# Backplane.net
KiCad netlist of a schematic drawn in EAGLE
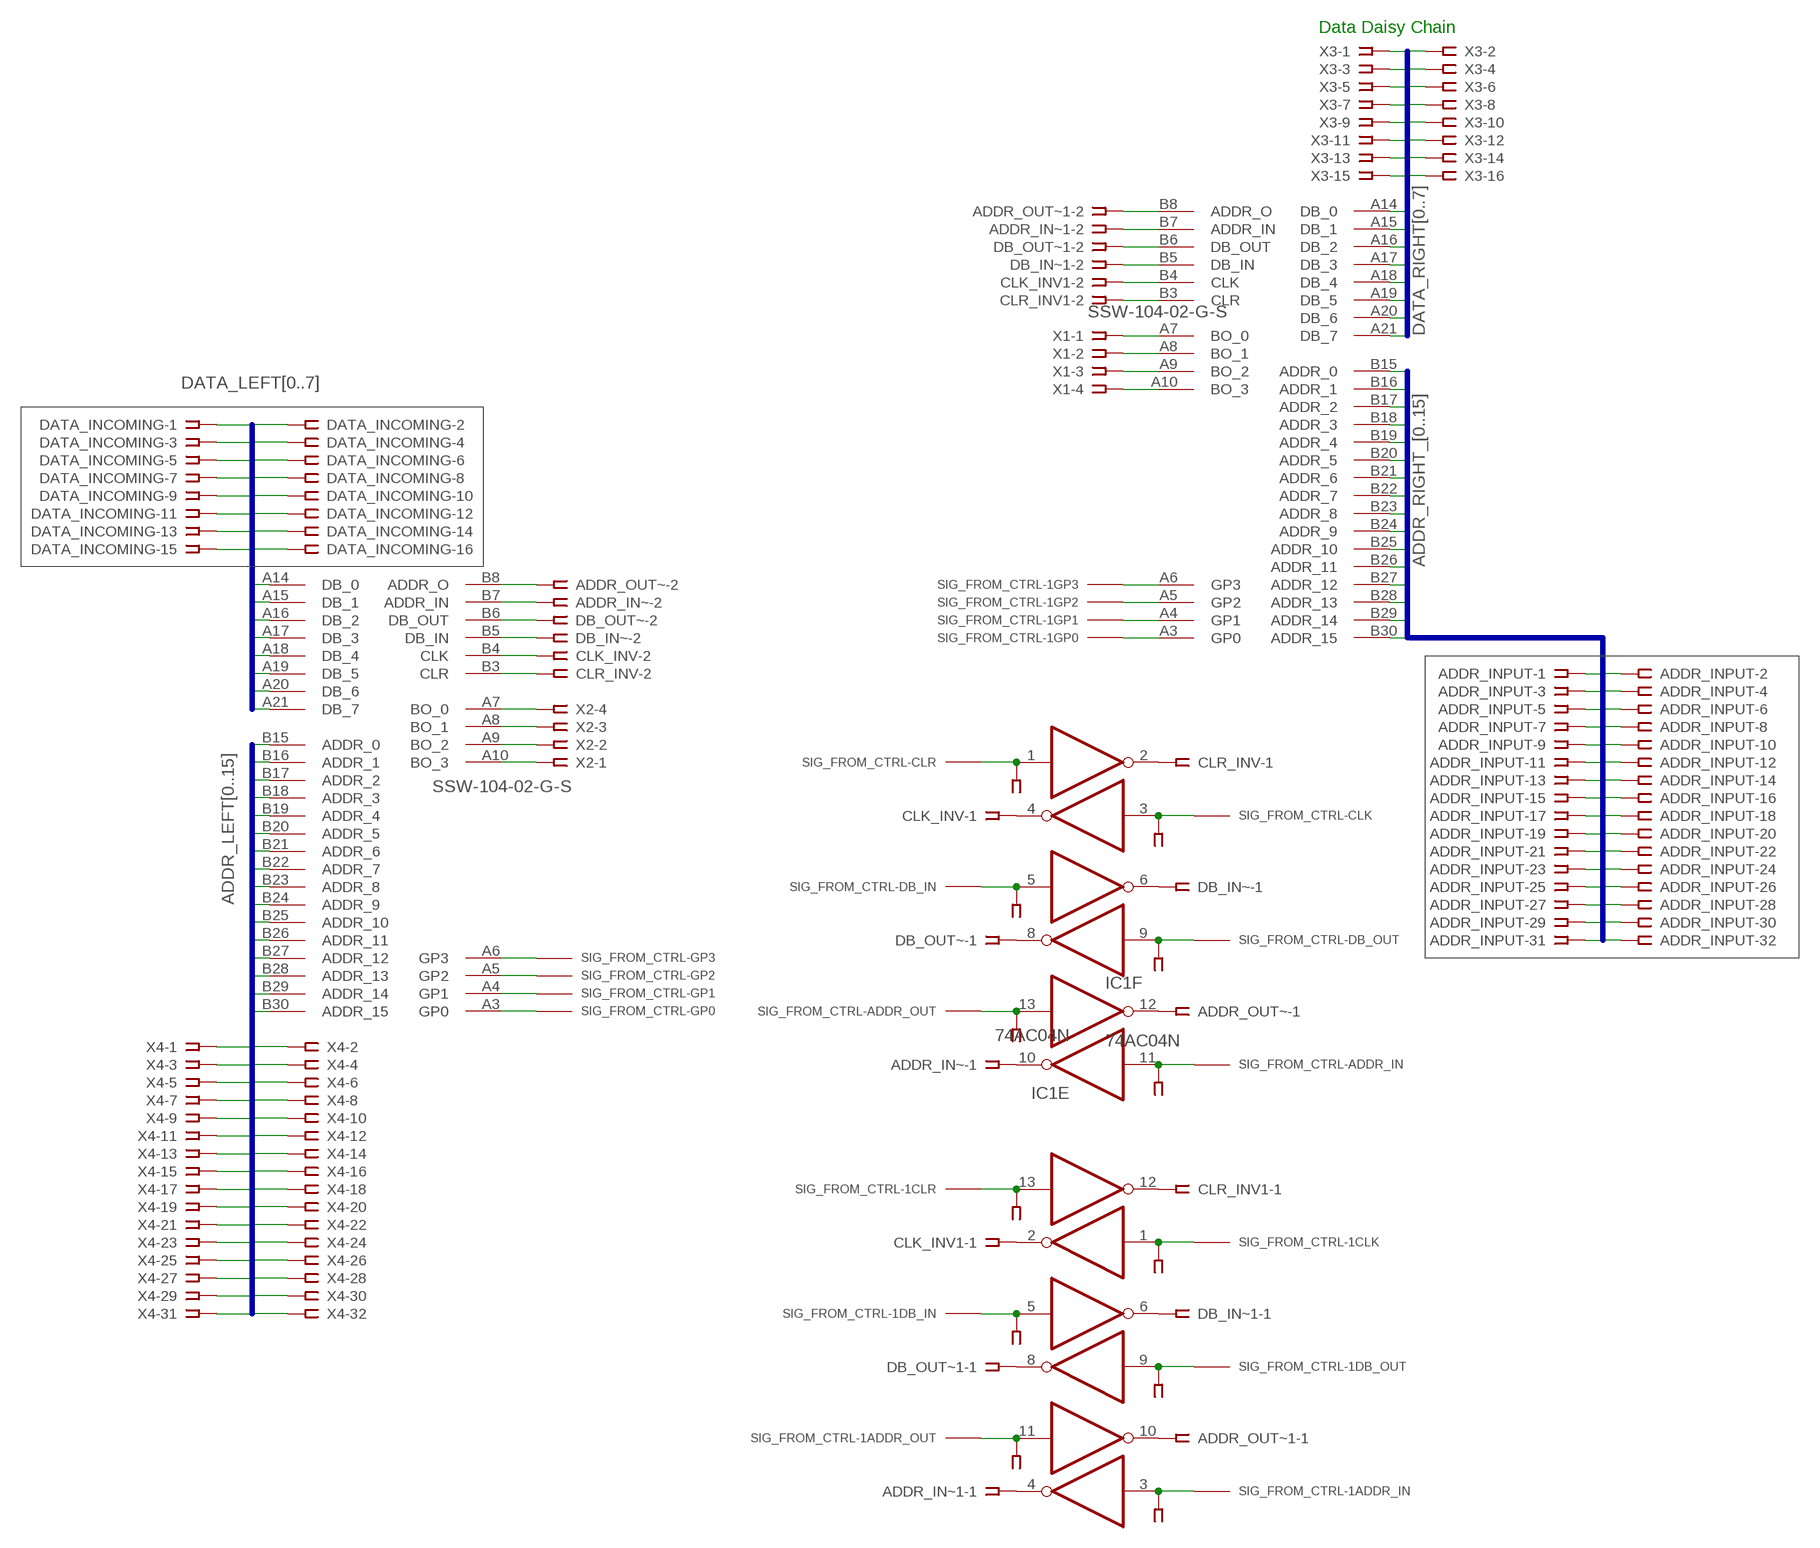
[diagram p0: schematic, sheet 1]

(export (version "E")
  (design (tool "Eeschema 10.0.6"))
  (components
    (comp (ref "ADDR_INPUT")
      (value "SSW-116-02-G-D")
      (footprint "eagle-import:SSW-116-02-G-D")
      (fields (field (name "MF") "Samtec Inc."))
      (libsource (lib "eagle-import") (part "SSW-116-02-G-D"))
    )
    (comp (ref "ADDR_IN~")
      (value "SSW-103-02-G-S")
      (footprint "eagle-import:SSW-103-02-G-S")
      (fields (field (name "MF") "Samtec Inc."))
      (libsource (lib "eagle-import") (part "SSW-103-02-G-S"))
    )
    (comp (ref "ADDR_IN~1")
      (value "SSW-103-02-G-S")
      (footprint "eagle-import:SSW-103-02-G-S")
      (fields (field (name "MF") "Samtec Inc."))
      (libsource (lib "eagle-import") (part "SSW-103-02-G-S"))
    )
    (comp (ref "ADDR_OUT~")
      (value "SSW-103-02-G-S")
      (footprint "eagle-import:SSW-103-02-G-S")
      (fields (field (name "MF") "Samtec Inc."))
      (libsource (lib "eagle-import") (part "SSW-103-02-G-S"))
    )
    (comp (ref "ADDR_OUT~1")
      (value "SSW-103-02-G-S")
      (footprint "eagle-import:SSW-103-02-G-S")
      (fields (field (name "MF") "Samtec Inc."))
      (libsource (lib "eagle-import") (part "SSW-103-02-G-S"))
    )
    (comp (ref "CLK_INV")
      (value "SSW-103-02-G-S")
      (footprint "eagle-import:SSW-103-02-G-S")
      (fields (field (name "MF") "Samtec Inc."))
      (libsource (lib "eagle-import") (part "SSW-103-02-G-S"))
    )
    (comp (ref "CLK_INV1")
      (value "SSW-103-02-G-S")
      (footprint "eagle-import:SSW-103-02-G-S")
      (fields (field (name "MF") "Samtec Inc."))
      (libsource (lib "eagle-import") (part "SSW-103-02-G-S"))
    )
    (comp (ref "CLR_INV")
      (value "SSW-103-02-G-S")
      (footprint "eagle-import:SSW-103-02-G-S")
      (fields (field (name "MF") "Samtec Inc."))
      (libsource (lib "eagle-import") (part "SSW-103-02-G-S"))
    )
    (comp (ref "CLR_INV1")
      (value "SSW-103-02-G-S")
      (footprint "eagle-import:SSW-103-02-G-S")
      (fields (field (name "MF") "Samtec Inc."))
      (libsource (lib "eagle-import") (part "SSW-103-02-G-S"))
    )
    (comp (ref "DATA_INCOMING")
      (value "SSW-108-02-G-D")
      (footprint "eagle-import:SSW-108-02-G-D")
      (fields (field (name "MF") "Samtec Inc."))
      (libsource (lib "eagle-import") (part "SSW-108-02-G-D"))
    )
    (comp (ref "DB_IN~")
      (value "SSW-103-02-G-S")
      (footprint "eagle-import:SSW-103-02-G-S")
      (fields (field (name "MF") "Samtec Inc."))
      (libsource (lib "eagle-import") (part "SSW-103-02-G-S"))
    )
    (comp (ref "DB_IN~1")
      (value "SSW-103-02-G-S")
      (footprint "eagle-import:SSW-103-02-G-S")
      (fields (field (name "MF") "Samtec Inc."))
      (libsource (lib "eagle-import") (part "SSW-103-02-G-S"))
    )
    (comp (ref "DB_OUT~")
      (value "SSW-103-02-G-S")
      (footprint "eagle-import:SSW-103-02-G-S")
      (fields (field (name "MF") "Samtec Inc."))
      (libsource (lib "eagle-import") (part "SSW-103-02-G-S"))
    )
    (comp (ref "DB_OUT~1")
      (value "SSW-103-02-G-S")
      (footprint "eagle-import:SSW-103-02-G-S")
      (fields (field (name "MF") "Samtec Inc."))
      (libsource (lib "eagle-import") (part "SSW-103-02-G-S"))
    )
    (comp (ref "IC1")
      (value "74AC04N")
      (footprint "eagle-import:DIL14")
      (libsource (lib "eagle-import") (part "7404NAC"))
    )
    (comp (ref "IC2")
      (value "74AC04N")
      (footprint "eagle-import:DIL14")
      (libsource (lib "eagle-import") (part "7404NAC"))
    )
    (comp (ref "SIG_FROM_CTRL-")
      (value "CONTROL_SIG-INT")
      (footprint "eagle-import:CONTROL_SIG-INT-FOOT")
      (libsource (lib "eagle-import") (part "CONTROL_SIG-INT"))
    )
    (comp (ref "SIG_FROM_CTRL-1")
      (value "CONTROL_SIG-INT")
      (footprint "eagle-import:CONTROL_SIG-INT-FOOT")
      (libsource (lib "eagle-import") (part "CONTROL_SIG-INT"))
    )
    (comp (ref "U$1")
      (value "BACKPLATE_INTERFACEHEADER")
      (footprint "eagle-import:PCI_INTERFACE")
      (libsource (lib "eagle-import") (part "BACKPLATE_INTERFACEHEADER"))
    )
    (comp (ref "U$2")
      (value "BACKPLATE_INTERFACEHEADER")
      (footprint "eagle-import:PCI_INTERFACE")
      (libsource (lib "eagle-import") (part "BACKPLATE_INTERFACEHEADER"))
    )
    (comp (ref "X1")
      (value "SSW-104-02-G-S")
      (footprint "eagle-import:SSW-104-02-G-S")
      (fields (field (name "MF") "Samtec Inc."))
      (libsource (lib "eagle-import") (part "SSW-104-02-G-S"))
    )
    (comp (ref "X2")
      (value "SSW-104-02-G-S")
      (footprint "eagle-import:SSW-104-02-G-S")
      (fields (field (name "MF") "Samtec Inc."))
      (libsource (lib "eagle-import") (part "SSW-104-02-G-S"))
    )
    (comp (ref "X3")
      (value "SSW-108-02-G-D")
      (footprint "eagle-import:SSW-108-02-G-D")
      (fields (field (name "MF") "Samtec Inc."))
      (libsource (lib "eagle-import") (part "SSW-108-02-G-D"))
    )
    (comp (ref "X4")
      (value "SSW-116-02-G-D")
      (footprint "eagle-import:SSW-116-02-G-D")
      (fields (field (name "MF") "Samtec Inc."))
      (libsource (lib "eagle-import") (part "SSW-116-02-G-D"))
    )
  )
  (nets
    (net (code "1") (name "/ADDR_LEFT0") (class "Default")
      (node (ref "U$2") (pin "B15") (pinfunction "ADDR_0_B15") (pintype "bidirectional"))
      (node (ref "X4") (pin "1") (pinfunction "1_1") (pintype "passive"))
      (node (ref "X4") (pin "2") (pinfunction "1_2") (pintype "passive"))
    )
    (net (code "2") (name "/ADDR_LEFT1") (class "Default")
      (node (ref "U$2") (pin "B16") (pinfunction "ADDR_1_B16") (pintype "bidirectional"))
      (node (ref "X4") (pin "3") (pinfunction "1_3") (pintype "passive"))
      (node (ref "X4") (pin "4") (pinfunction "1_4") (pintype "passive"))
    )
    (net (code "3") (name "/ADDR_LEFT2") (class "Default")
      (node (ref "U$2") (pin "B17") (pinfunction "ADDR_2_B17") (pintype "bidirectional"))
      (node (ref "X4") (pin "5") (pinfunction "1_5") (pintype "passive"))
      (node (ref "X4") (pin "6") (pinfunction "1_6") (pintype "passive"))
    )
    (net (code "4") (name "/ADDR_LEFT3") (class "Default")
      (node (ref "U$2") (pin "B18") (pinfunction "ADDR_3_B18") (pintype "bidirectional"))
      (node (ref "X4") (pin "7") (pinfunction "1_7") (pintype "passive"))
      (node (ref "X4") (pin "8") (pinfunction "1_8") (pintype "passive"))
    )
    (net (code "5") (name "/ADDR_LEFT4") (class "Default")
      (node (ref "U$2") (pin "B19") (pinfunction "ADDR_4_B19") (pintype "bidirectional"))
      (node (ref "X4") (pin "10") (pinfunction "1_10") (pintype "passive"))
      (node (ref "X4") (pin "9") (pinfunction "1_9") (pintype "passive"))
    )
    (net (code "6") (name "/ADDR_LEFT5") (class "Default")
      (node (ref "U$2") (pin "B20") (pinfunction "ADDR_5_B20") (pintype "bidirectional"))
      (node (ref "X4") (pin "11") (pinfunction "1_11") (pintype "passive"))
      (node (ref "X4") (pin "12") (pinfunction "1_12") (pintype "passive"))
    )
    (net (code "7") (name "/ADDR_LEFT6") (class "Default")
      (node (ref "U$2") (pin "B21") (pinfunction "ADDR_6_B21") (pintype "bidirectional"))
      (node (ref "X4") (pin "13") (pinfunction "1_13") (pintype "passive"))
      (node (ref "X4") (pin "14") (pinfunction "1_14") (pintype "passive"))
    )
    (net (code "8") (name "/ADDR_LEFT7") (class "Default")
      (node (ref "U$2") (pin "B22") (pinfunction "ADDR_7_B22") (pintype "bidirectional"))
      (node (ref "X4") (pin "15") (pinfunction "1_15") (pintype "passive"))
      (node (ref "X4") (pin "16") (pinfunction "1_16") (pintype "passive"))
    )
    (net (code "9") (name "/ADDR_LEFT8") (class "Default")
      (node (ref "U$2") (pin "B23") (pinfunction "ADDR_8_B23") (pintype "bidirectional"))
      (node (ref "X4") (pin "17") (pinfunction "1_17") (pintype "passive"))
      (node (ref "X4") (pin "18") (pinfunction "1_18") (pintype "passive"))
    )
    (net (code "10") (name "/ADDR_LEFT9") (class "Default")
      (node (ref "U$2") (pin "B24") (pinfunction "ADDR_9_B24") (pintype "bidirectional"))
      (node (ref "X4") (pin "19") (pinfunction "1_19") (pintype "passive"))
      (node (ref "X4") (pin "20") (pinfunction "1_20") (pintype "passive"))
    )
    (net (code "11") (name "/ADDR_LEFT10") (class "Default")
      (node (ref "U$2") (pin "B25") (pinfunction "ADDR_10_B25") (pintype "bidirectional"))
      (node (ref "X4") (pin "21") (pinfunction "1_21") (pintype "passive"))
      (node (ref "X4") (pin "22") (pinfunction "1_22") (pintype "passive"))
    )
    (net (code "12") (name "/ADDR_LEFT11") (class "Default")
      (node (ref "U$2") (pin "B26") (pinfunction "ADDR_11_B26") (pintype "bidirectional"))
      (node (ref "X4") (pin "23") (pinfunction "1_23") (pintype "passive"))
      (node (ref "X4") (pin "24") (pinfunction "1_24") (pintype "passive"))
    )
    (net (code "13") (name "/ADDR_LEFT12") (class "Default")
      (node (ref "U$2") (pin "B27") (pinfunction "ADDR_12_B27") (pintype "bidirectional"))
      (node (ref "X4") (pin "25") (pinfunction "1_25") (pintype "passive"))
      (node (ref "X4") (pin "26") (pinfunction "1_26") (pintype "passive"))
    )
    (net (code "14") (name "/ADDR_LEFT13") (class "Default")
      (node (ref "U$2") (pin "B28") (pinfunction "ADDR_13_B28") (pintype "bidirectional"))
      (node (ref "X4") (pin "27") (pinfunction "1_27") (pintype "passive"))
      (node (ref "X4") (pin "28") (pinfunction "1_28") (pintype "passive"))
    )
    (net (code "15") (name "/ADDR_LEFT14") (class "Default")
      (node (ref "U$2") (pin "B29") (pinfunction "ADDR_14_B29") (pintype "bidirectional"))
      (node (ref "X4") (pin "29") (pinfunction "1_29") (pintype "passive"))
      (node (ref "X4") (pin "30") (pinfunction "1_30") (pintype "passive"))
    )
    (net (code "16") (name "/ADDR_LEFT15") (class "Default")
      (node (ref "U$2") (pin "B30") (pinfunction "ADDR_15_B30") (pintype "bidirectional"))
      (node (ref "X4") (pin "31") (pinfunction "1_31") (pintype "passive"))
      (node (ref "X4") (pin "32") (pinfunction "1_32") (pintype "passive"))
    )
    (net (code "18") (name "/ADDR_RIGHT_0") (class "Default")
      (node (ref "ADDR_INPUT") (pin "1") (pinfunction "1_1") (pintype "passive"))
      (node (ref "ADDR_INPUT") (pin "2") (pinfunction "1_2") (pintype "passive"))
      (node (ref "U$1") (pin "B15") (pinfunction "ADDR_0_B15") (pintype "bidirectional"))
    )
    (net (code "19") (name "/ADDR_RIGHT_1") (class "Default")
      (node (ref "ADDR_INPUT") (pin "3") (pinfunction "1_3") (pintype "passive"))
      (node (ref "ADDR_INPUT") (pin "4") (pinfunction "1_4") (pintype "passive"))
      (node (ref "U$1") (pin "B16") (pinfunction "ADDR_1_B16") (pintype "bidirectional"))
    )
    (net (code "20") (name "/ADDR_RIGHT_2") (class "Default")
      (node (ref "ADDR_INPUT") (pin "5") (pinfunction "1_5") (pintype "passive"))
      (node (ref "ADDR_INPUT") (pin "6") (pinfunction "1_6") (pintype "passive"))
      (node (ref "U$1") (pin "B17") (pinfunction "ADDR_2_B17") (pintype "bidirectional"))
    )
    (net (code "21") (name "/ADDR_RIGHT_3") (class "Default")
      (node (ref "ADDR_INPUT") (pin "7") (pinfunction "1_7") (pintype "passive"))
      (node (ref "ADDR_INPUT") (pin "8") (pinfunction "1_8") (pintype "passive"))
      (node (ref "U$1") (pin "B18") (pinfunction "ADDR_3_B18") (pintype "bidirectional"))
    )
    (net (code "22") (name "/ADDR_RIGHT_4") (class "Default")
      (node (ref "ADDR_INPUT") (pin "10") (pinfunction "1_10") (pintype "passive"))
      (node (ref "ADDR_INPUT") (pin "9") (pinfunction "1_9") (pintype "passive"))
      (node (ref "U$1") (pin "B19") (pinfunction "ADDR_4_B19") (pintype "bidirectional"))
    )
    (net (code "23") (name "/ADDR_RIGHT_5") (class "Default")
      (node (ref "ADDR_INPUT") (pin "11") (pinfunction "1_11") (pintype "passive"))
      (node (ref "ADDR_INPUT") (pin "12") (pinfunction "1_12") (pintype "passive"))
      (node (ref "U$1") (pin "B20") (pinfunction "ADDR_5_B20") (pintype "bidirectional"))
    )
    (net (code "24") (name "/ADDR_RIGHT_6") (class "Default")
      (node (ref "ADDR_INPUT") (pin "13") (pinfunction "1_13") (pintype "passive"))
      (node (ref "ADDR_INPUT") (pin "14") (pinfunction "1_14") (pintype "passive"))
      (node (ref "U$1") (pin "B21") (pinfunction "ADDR_6_B21") (pintype "bidirectional"))
    )
    (net (code "25") (name "/ADDR_RIGHT_7") (class "Default")
      (node (ref "ADDR_INPUT") (pin "15") (pinfunction "1_15") (pintype "passive"))
      (node (ref "ADDR_INPUT") (pin "16") (pinfunction "1_16") (pintype "passive"))
      (node (ref "U$1") (pin "B22") (pinfunction "ADDR_7_B22") (pintype "bidirectional"))
    )
    (net (code "26") (name "/ADDR_RIGHT_8") (class "Default")
      (node (ref "ADDR_INPUT") (pin "17") (pinfunction "1_17") (pintype "passive"))
      (node (ref "ADDR_INPUT") (pin "18") (pinfunction "1_18") (pintype "passive"))
      (node (ref "U$1") (pin "B23") (pinfunction "ADDR_8_B23") (pintype "bidirectional"))
    )
    (net (code "27") (name "/ADDR_RIGHT_9") (class "Default")
      (node (ref "ADDR_INPUT") (pin "19") (pinfunction "1_19") (pintype "passive"))
      (node (ref "ADDR_INPUT") (pin "20") (pinfunction "1_20") (pintype "passive"))
      (node (ref "U$1") (pin "B24") (pinfunction "ADDR_9_B24") (pintype "bidirectional"))
    )
    (net (code "28") (name "/ADDR_RIGHT_10") (class "Default")
      (node (ref "ADDR_INPUT") (pin "21") (pinfunction "1_21") (pintype "passive"))
      (node (ref "ADDR_INPUT") (pin "22") (pinfunction "1_22") (pintype "passive"))
      (node (ref "U$1") (pin "B25") (pinfunction "ADDR_10_B25") (pintype "bidirectional"))
    )
    (net (code "29") (name "/ADDR_RIGHT_11") (class "Default")
      (node (ref "ADDR_INPUT") (pin "23") (pinfunction "1_23") (pintype "passive"))
      (node (ref "ADDR_INPUT") (pin "24") (pinfunction "1_24") (pintype "passive"))
      (node (ref "U$1") (pin "B26") (pinfunction "ADDR_11_B26") (pintype "bidirectional"))
    )
    (net (code "30") (name "/ADDR_RIGHT_12") (class "Default")
      (node (ref "ADDR_INPUT") (pin "25") (pinfunction "1_25") (pintype "passive"))
      (node (ref "ADDR_INPUT") (pin "26") (pinfunction "1_26") (pintype "passive"))
      (node (ref "U$1") (pin "B27") (pinfunction "ADDR_12_B27") (pintype "bidirectional"))
    )
    (net (code "31") (name "/ADDR_RIGHT_13") (class "Default")
      (node (ref "ADDR_INPUT") (pin "27") (pinfunction "1_27") (pintype "passive"))
      (node (ref "ADDR_INPUT") (pin "28") (pinfunction "1_28") (pintype "passive"))
      (node (ref "U$1") (pin "B28") (pinfunction "ADDR_13_B28") (pintype "bidirectional"))
    )
    (net (code "32") (name "/ADDR_RIGHT_14") (class "Default")
      (node (ref "ADDR_INPUT") (pin "29") (pinfunction "1_29") (pintype "passive"))
      (node (ref "ADDR_INPUT") (pin "30") (pinfunction "1_30") (pintype "passive"))
      (node (ref "U$1") (pin "B29") (pinfunction "ADDR_14_B29") (pintype "bidirectional"))
    )
    (net (code "33") (name "/ADDR_RIGHT_15") (class "Default")
      (node (ref "ADDR_INPUT") (pin "31") (pinfunction "1_31") (pintype "passive"))
      (node (ref "ADDR_INPUT") (pin "32") (pinfunction "1_32") (pintype "passive"))
      (node (ref "U$1") (pin "B30") (pinfunction "ADDR_15_B30") (pintype "bidirectional"))
    )
    (net (code "35") (name "/DATA_LEFT0") (class "Default")
      (node (ref "DATA_INCOMING") (pin "1") (pinfunction "1_1") (pintype "passive"))
      (node (ref "DATA_INCOMING") (pin "2") (pinfunction "1_2") (pintype "passive"))
      (node (ref "U$2") (pin "A14") (pinfunction "DB_0_A14") (pintype "bidirectional"))
    )
    (net (code "36") (name "/DATA_LEFT1") (class "Default")
      (node (ref "DATA_INCOMING") (pin "3") (pinfunction "1_3") (pintype "passive"))
      (node (ref "DATA_INCOMING") (pin "4") (pinfunction "1_4") (pintype "passive"))
      (node (ref "U$2") (pin "A15") (pinfunction "DB_1_A15") (pintype "bidirectional"))
    )
    (net (code "37") (name "/DATA_LEFT2") (class "Default")
      (node (ref "DATA_INCOMING") (pin "5") (pinfunction "1_5") (pintype "passive"))
      (node (ref "DATA_INCOMING") (pin "6") (pinfunction "1_6") (pintype "passive"))
      (node (ref "U$2") (pin "A16") (pinfunction "DB_2_A16") (pintype "bidirectional"))
    )
    (net (code "38") (name "/DATA_LEFT3") (class "Default")
      (node (ref "DATA_INCOMING") (pin "7") (pinfunction "1_7") (pintype "passive"))
      (node (ref "DATA_INCOMING") (pin "8") (pinfunction "1_8") (pintype "passive"))
      (node (ref "U$2") (pin "A17") (pinfunction "DB_3_A17") (pintype "bidirectional"))
    )
    (net (code "39") (name "/DATA_LEFT4") (class "Default")
      (node (ref "DATA_INCOMING") (pin "10") (pinfunction "1_10") (pintype "passive"))
      (node (ref "DATA_INCOMING") (pin "9") (pinfunction "1_9") (pintype "passive"))
      (node (ref "U$2") (pin "A18") (pinfunction "DB_4_A18") (pintype "bidirectional"))
    )
    (net (code "40") (name "/DATA_LEFT5") (class "Default")
      (node (ref "DATA_INCOMING") (pin "11") (pinfunction "1_11") (pintype "passive"))
      (node (ref "DATA_INCOMING") (pin "12") (pinfunction "1_12") (pintype "passive"))
      (node (ref "U$2") (pin "A19") (pinfunction "DB_5_A19") (pintype "bidirectional"))
    )
    (net (code "41") (name "/DATA_LEFT6") (class "Default")
      (node (ref "DATA_INCOMING") (pin "13") (pinfunction "1_13") (pintype "passive"))
      (node (ref "DATA_INCOMING") (pin "14") (pinfunction "1_14") (pintype "passive"))
      (node (ref "U$2") (pin "A20") (pinfunction "DB_6_A20") (pintype "bidirectional"))
    )
    (net (code "42") (name "/DATA_LEFT7") (class "Default")
      (node (ref "DATA_INCOMING") (pin "15") (pinfunction "1_15") (pintype "passive"))
      (node (ref "DATA_INCOMING") (pin "16") (pinfunction "1_16") (pintype "passive"))
      (node (ref "U$2") (pin "A21") (pinfunction "DB_7_A21") (pintype "bidirectional"))
    )
    (net (code "43") (name "/DATA_RIGHT0") (class "Default")
      (node (ref "U$1") (pin "A14") (pinfunction "DB_0_A14") (pintype "bidirectional"))
      (node (ref "X3") (pin "1") (pinfunction "1_1") (pintype "passive"))
      (node (ref "X3") (pin "2") (pinfunction "1_2") (pintype "passive"))
    )
    (net (code "44") (name "/DATA_RIGHT1") (class "Default")
      (node (ref "U$1") (pin "A15") (pinfunction "DB_1_A15") (pintype "bidirectional"))
      (node (ref "X3") (pin "3") (pinfunction "1_3") (pintype "passive"))
      (node (ref "X3") (pin "4") (pinfunction "1_4") (pintype "passive"))
    )
    (net (code "45") (name "/DATA_RIGHT2") (class "Default")
      (node (ref "U$1") (pin "A16") (pinfunction "DB_2_A16") (pintype "bidirectional"))
      (node (ref "X3") (pin "5") (pinfunction "1_5") (pintype "passive"))
      (node (ref "X3") (pin "6") (pinfunction "1_6") (pintype "passive"))
    )
    (net (code "46") (name "/DATA_RIGHT3") (class "Default")
      (node (ref "U$1") (pin "A17") (pinfunction "DB_3_A17") (pintype "bidirectional"))
      (node (ref "X3") (pin "7") (pinfunction "1_7") (pintype "passive"))
      (node (ref "X3") (pin "8") (pinfunction "1_8") (pintype "passive"))
    )
    (net (code "47") (name "/DATA_RIGHT4") (class "Default")
      (node (ref "U$1") (pin "A18") (pinfunction "DB_4_A18") (pintype "bidirectional"))
      (node (ref "X3") (pin "10") (pinfunction "1_10") (pintype "passive"))
      (node (ref "X3") (pin "9") (pinfunction "1_9") (pintype "passive"))
    )
    (net (code "48") (name "/DATA_RIGHT5") (class "Default")
      (node (ref "U$1") (pin "A19") (pinfunction "DB_5_A19") (pintype "bidirectional"))
      (node (ref "X3") (pin "11") (pinfunction "1_11") (pintype "passive"))
      (node (ref "X3") (pin "12") (pinfunction "1_12") (pintype "passive"))
    )
    (net (code "49") (name "/DATA_RIGHT6") (class "Default")
      (node (ref "U$1") (pin "A20") (pinfunction "DB_6_A20") (pintype "bidirectional"))
      (node (ref "X3") (pin "13") (pinfunction "1_13") (pintype "passive"))
      (node (ref "X3") (pin "14") (pinfunction "1_14") (pintype "passive"))
    )
    (net (code "50") (name "/DATA_RIGHT7") (class "Default")
      (node (ref "U$1") (pin "A21") (pinfunction "DB_7_A21") (pintype "bidirectional"))
      (node (ref "X3") (pin "15") (pinfunction "1_15") (pintype "passive"))
      (node (ref "X3") (pin "16") (pinfunction "1_16") (pintype "passive"))
    )
    (net (code "52") (name "Net-(ADDR_IN~1B-1)") (class "Default")
      (node (ref "ADDR_IN~1") (pin "2") (pinfunction "1_2") (pintype "passive"))
      (node (ref "U$1") (pin "B7") (pinfunction "ADDR_IN_B7") (pintype "bidirectional"))
    )
    (net (code "53") (name "Net-(ADDR_IN~1C-1)") (class "Default")
      (node (ref "ADDR_IN~1") (pin "3") (pinfunction "1_3") (pintype "passive"))
      (node (ref "IC2") (pin "3") (pinfunction "I_3") (pintype "input"))
      (node (ref "SIG_FROM_CTRL-1") (pin "ADDR_IN") (pinfunction "0_ADDR_IN") (pintype "bidirectional"))
    )
    (net (code "54") (name "Net-(ADDR_IN~B-1)") (class "Default")
      (node (ref "ADDR_IN~") (pin "2") (pinfunction "1_2") (pintype "passive"))
      (node (ref "U$2") (pin "B7") (pinfunction "ADDR_IN_B7") (pintype "bidirectional"))
    )
    (net (code "55") (name "Net-(ADDR_IN~C-1)") (class "Default")
      (node (ref "ADDR_IN~") (pin "3") (pinfunction "1_3") (pintype "passive"))
      (node (ref "IC1") (pin "11") (pinfunction "I_11") (pintype "input"))
      (node (ref "SIG_FROM_CTRL-") (pin "ADDR_IN") (pinfunction "0_ADDR_IN") (pintype "bidirectional"))
    )
    (net (code "56") (name "Net-(ADDR_OUT~1B-1)") (class "Default")
      (node (ref "ADDR_OUT~1") (pin "2") (pinfunction "1_2") (pintype "passive"))
      (node (ref "U$1") (pin "B8") (pinfunction "ADDR_O_B8") (pintype "bidirectional"))
    )
    (net (code "57") (name "Net-(ADDR_OUT~1C-1)") (class "Default")
      (node (ref "ADDR_OUT~1") (pin "3") (pinfunction "1_3") (pintype "passive"))
      (node (ref "IC2") (pin "11") (pinfunction "I_11") (pintype "input"))
      (node (ref "SIG_FROM_CTRL-1") (pin "ADDR_OT") (pinfunction "0_ADDR_OT") (pintype "bidirectional"))
    )
    (net (code "58") (name "Net-(ADDR_OUT~B-1)") (class "Default")
      (node (ref "ADDR_OUT~") (pin "2") (pinfunction "1_2") (pintype "passive"))
      (node (ref "U$2") (pin "B8") (pinfunction "ADDR_O_B8") (pintype "bidirectional"))
    )
    (net (code "59") (name "Net-(ADDR_OUT~C-1)") (class "Default")
      (node (ref "ADDR_OUT~") (pin "3") (pinfunction "1_3") (pintype "passive"))
      (node (ref "IC1") (pin "13") (pinfunction "I_13") (pintype "input"))
      (node (ref "SIG_FROM_CTRL-") (pin "ADDR_OT") (pinfunction "0_ADDR_OT") (pintype "bidirectional"))
    )
    (net (code "60") (name "Net-(CLK_INV1B-1)") (class "Default")
      (node (ref "CLK_INV1") (pin "2") (pinfunction "1_2") (pintype "passive"))
      (node (ref "U$1") (pin "B4") (pinfunction "CLK_B4") (pintype "bidirectional"))
    )
    (net (code "61") (name "Net-(CLK_INV1C-1)") (class "Default")
      (node (ref "CLK_INV1") (pin "3") (pinfunction "1_3") (pintype "passive"))
      (node (ref "IC2") (pin "1") (pinfunction "I_1") (pintype "input"))
      (node (ref "SIG_FROM_CTRL-1") (pin "CLK") (pinfunction "0_CLK") (pintype "bidirectional"))
    )
    (net (code "62") (name "Net-(CLK_INVB-1)") (class "Default")
      (node (ref "CLK_INV") (pin "2") (pinfunction "1_2") (pintype "passive"))
      (node (ref "U$2") (pin "B4") (pinfunction "CLK_B4") (pintype "bidirectional"))
    )
    (net (code "63") (name "Net-(CLK_INVC-1)") (class "Default")
      (node (ref "CLK_INV") (pin "3") (pinfunction "1_3") (pintype "passive"))
      (node (ref "IC1") (pin "3") (pinfunction "I_3") (pintype "input"))
      (node (ref "SIG_FROM_CTRL-") (pin "CLK") (pinfunction "0_CLK") (pintype "bidirectional"))
    )
    (net (code "64") (name "Net-(CLR_INV1B-1)") (class "Default")
      (node (ref "CLR_INV1") (pin "2") (pinfunction "1_2") (pintype "passive"))
      (node (ref "U$1") (pin "B3") (pinfunction "CLR_B3") (pintype "bidirectional"))
    )
    (net (code "65") (name "Net-(CLR_INV1C-1)") (class "Default")
      (node (ref "CLR_INV1") (pin "3") (pinfunction "1_3") (pintype "passive"))
      (node (ref "IC2") (pin "13") (pinfunction "I_13") (pintype "input"))
      (node (ref "SIG_FROM_CTRL-1") (pin "CLR") (pinfunction "0_CLR") (pintype "bidirectional"))
    )
    (net (code "66") (name "Net-(CLR_INVB-1)") (class "Default")
      (node (ref "CLR_INV") (pin "2") (pinfunction "1_2") (pintype "passive"))
      (node (ref "U$2") (pin "B3") (pinfunction "CLR_B3") (pintype "bidirectional"))
    )
    (net (code "67") (name "Net-(CLR_INVC-1)") (class "Default")
      (node (ref "CLR_INV") (pin "3") (pinfunction "1_3") (pintype "passive"))
      (node (ref "IC1") (pin "1") (pinfunction "I_1") (pintype "input"))
      (node (ref "SIG_FROM_CTRL-") (pin "CLR") (pinfunction "0_CLR") (pintype "bidirectional"))
    )
    (net (code "68") (name "Net-(DB_IN~1B-1)") (class "Default")
      (node (ref "DB_IN~1") (pin "2") (pinfunction "1_2") (pintype "passive"))
      (node (ref "U$1") (pin "B5") (pinfunction "DB_IN_B5") (pintype "bidirectional"))
    )
    (net (code "69") (name "Net-(DB_IN~1C-1)") (class "Default")
      (node (ref "DB_IN~1") (pin "3") (pinfunction "1_3") (pintype "passive"))
      (node (ref "IC2") (pin "5") (pinfunction "I_5") (pintype "input"))
      (node (ref "SIG_FROM_CTRL-1") (pin "DB_IN") (pinfunction "0_DB_IN") (pintype "bidirectional"))
    )
    (net (code "70") (name "Net-(DB_IN~B-1)") (class "Default")
      (node (ref "DB_IN~") (pin "2") (pinfunction "1_2") (pintype "passive"))
      (node (ref "U$2") (pin "B5") (pinfunction "DB_IN_B5") (pintype "bidirectional"))
    )
    (net (code "71") (name "Net-(DB_IN~C-1)") (class "Default")
      (node (ref "DB_IN~") (pin "3") (pinfunction "1_3") (pintype "passive"))
      (node (ref "IC1") (pin "5") (pinfunction "I_5") (pintype "input"))
      (node (ref "SIG_FROM_CTRL-") (pin "DB_IN") (pinfunction "0_DB_IN") (pintype "bidirectional"))
    )
    (net (code "72") (name "Net-(DB_OUT~1B-1)") (class "Default")
      (node (ref "DB_OUT~1") (pin "2") (pinfunction "1_2") (pintype "passive"))
      (node (ref "U$1") (pin "B6") (pinfunction "DB_OUT_B6") (pintype "bidirectional"))
    )
    (net (code "73") (name "Net-(DB_OUT~1C-1)") (class "Default")
      (node (ref "DB_OUT~1") (pin "3") (pinfunction "1_3") (pintype "passive"))
      (node (ref "IC2") (pin "9") (pinfunction "I_9") (pintype "input"))
      (node (ref "SIG_FROM_CTRL-1") (pin "DB_OUT") (pinfunction "0_DB_OUT") (pintype "bidirectional"))
    )
    (net (code "74") (name "Net-(DB_OUT~B-1)") (class "Default")
      (node (ref "DB_OUT~") (pin "2") (pinfunction "1_2") (pintype "passive"))
      (node (ref "U$2") (pin "B6") (pinfunction "DB_OUT_B6") (pintype "bidirectional"))
    )
    (net (code "75") (name "Net-(DB_OUT~C-1)") (class "Default")
      (node (ref "DB_OUT~") (pin "3") (pinfunction "1_3") (pintype "passive"))
      (node (ref "IC1") (pin "9") (pinfunction "I_9") (pintype "input"))
      (node (ref "SIG_FROM_CTRL-") (pin "DB_OUT") (pinfunction "0_DB_OUT") (pintype "bidirectional"))
    )
    (net (code "76") (name "Net-(IC1A-O)") (class "Default")
      (node (ref "CLR_INV") (pin "1") (pinfunction "1_1") (pintype "passive"))
      (node (ref "IC1") (pin "2") (pinfunction "O_2") (pintype "output"))
    )
    (net (code "77") (name "Net-(IC1B-O)") (class "Default")
      (node (ref "CLK_INV") (pin "1") (pinfunction "1_1") (pintype "passive"))
      (node (ref "IC1") (pin "4") (pinfunction "O_4") (pintype "output"))
    )
    (net (code "78") (name "Net-(IC1C-O)") (class "Default")
      (node (ref "DB_IN~") (pin "1") (pinfunction "1_1") (pintype "passive"))
      (node (ref "IC1") (pin "6") (pinfunction "O_6") (pintype "output"))
    )
    (net (code "79") (name "Net-(IC1D-O)") (class "Default")
      (node (ref "DB_OUT~") (pin "1") (pinfunction "1_1") (pintype "passive"))
      (node (ref "IC1") (pin "8") (pinfunction "O_8") (pintype "output"))
    )
    (net (code "80") (name "Net-(IC1E-O)") (class "Default")
      (node (ref "ADDR_IN~") (pin "1") (pinfunction "1_1") (pintype "passive"))
      (node (ref "IC1") (pin "10") (pinfunction "O_10") (pintype "output"))
    )
    (net (code "81") (name "Net-(IC1F-O)") (class "Default")
      (node (ref "ADDR_OUT~") (pin "1") (pinfunction "1_1") (pintype "passive"))
      (node (ref "IC1") (pin "12") (pinfunction "O_12") (pintype "output"))
    )
    (net (code "82") (name "Net-(IC2A-O)") (class "Default")
      (node (ref "CLK_INV1") (pin "1") (pinfunction "1_1") (pintype "passive"))
      (node (ref "IC2") (pin "2") (pinfunction "O_2") (pintype "output"))
    )
    (net (code "83") (name "Net-(IC2B-O)") (class "Default")
      (node (ref "ADDR_IN~1") (pin "1") (pinfunction "1_1") (pintype "passive"))
      (node (ref "IC2") (pin "4") (pinfunction "O_4") (pintype "output"))
    )
    (net (code "84") (name "Net-(IC2C-O)") (class "Default")
      (node (ref "DB_IN~1") (pin "1") (pinfunction "1_1") (pintype "passive"))
      (node (ref "IC2") (pin "6") (pinfunction "O_6") (pintype "output"))
    )
    (net (code "85") (name "Net-(IC2D-O)") (class "Default")
      (node (ref "DB_OUT~1") (pin "1") (pinfunction "1_1") (pintype "passive"))
      (node (ref "IC2") (pin "8") (pinfunction "O_8") (pintype "output"))
    )
    (net (code "86") (name "Net-(IC2E-O)") (class "Default")
      (node (ref "ADDR_OUT~1") (pin "1") (pinfunction "1_1") (pintype "passive"))
      (node (ref "IC2") (pin "10") (pinfunction "O_10") (pintype "output"))
    )
    (net (code "87") (name "Net-(IC2F-O)") (class "Default")
      (node (ref "CLR_INV1") (pin "1") (pinfunction "1_1") (pintype "passive"))
      (node (ref "IC2") (pin "12") (pinfunction "O_12") (pintype "output"))
    )
    (net (code "88") (name "Net-(SIG_FROM_CTRL-1H-0)") (class "Default")
      (node (ref "SIG_FROM_CTRL-1") (pin "GP0") (pinfunction "0_GP0") (pintype "bidirectional"))
      (node (ref "U$1") (pin "A3") (pinfunction "GP0_A3") (pintype "bidirectional"))
    )
    (net (code "89") (name "Net-(SIG_FROM_CTRL-1I-0)") (class "Default")
      (node (ref "SIG_FROM_CTRL-1") (pin "GP1") (pinfunction "0_GP1") (pintype "bidirectional"))
      (node (ref "U$1") (pin "A4") (pinfunction "GP1_A4") (pintype "bidirectional"))
    )
    (net (code "90") (name "Net-(SIG_FROM_CTRL-1J-0)") (class "Default")
      (node (ref "SIG_FROM_CTRL-1") (pin "GP2") (pinfunction "0_GP2") (pintype "bidirectional"))
      (node (ref "U$1") (pin "A5") (pinfunction "GP2_A5") (pintype "bidirectional"))
    )
    (net (code "91") (name "Net-(SIG_FROM_CTRL-1K-0)") (class "Default")
      (node (ref "SIG_FROM_CTRL-1") (pin "GP3") (pinfunction "0_GP3") (pintype "bidirectional"))
      (node (ref "U$1") (pin "A6") (pinfunction "GP3_A6") (pintype "bidirectional"))
    )
    (net (code "92") (name "Net-(SIG_FROM_CTRL-H-0)") (class "Default")
      (node (ref "SIG_FROM_CTRL-") (pin "GP0") (pinfunction "0_GP0") (pintype "bidirectional"))
      (node (ref "U$2") (pin "A3") (pinfunction "GP0_A3") (pintype "bidirectional"))
    )
    (net (code "93") (name "Net-(SIG_FROM_CTRL-I-0)") (class "Default")
      (node (ref "SIG_FROM_CTRL-") (pin "GP1") (pinfunction "0_GP1") (pintype "bidirectional"))
      (node (ref "U$2") (pin "A4") (pinfunction "GP1_A4") (pintype "bidirectional"))
    )
    (net (code "94") (name "Net-(SIG_FROM_CTRL-J-0)") (class "Default")
      (node (ref "SIG_FROM_CTRL-") (pin "GP2") (pinfunction "0_GP2") (pintype "bidirectional"))
      (node (ref "U$2") (pin "A5") (pinfunction "GP2_A5") (pintype "bidirectional"))
    )
    (net (code "95") (name "Net-(SIG_FROM_CTRL-K-0)") (class "Default")
      (node (ref "SIG_FROM_CTRL-") (pin "GP3") (pinfunction "0_GP3") (pintype "bidirectional"))
      (node (ref "U$2") (pin "A6") (pinfunction "GP3_A6") (pintype "bidirectional"))
    )
    (net (code "96") (name "Net-(U$1A-BO_0)") (class "Default")
      (node (ref "U$1") (pin "A7") (pinfunction "BO_0_A7") (pintype "bidirectional"))
      (node (ref "X1") (pin "1") (pinfunction "1_1") (pintype "passive"))
    )
    (net (code "97") (name "Net-(U$1A-BO_1)") (class "Default")
      (node (ref "U$1") (pin "A8") (pinfunction "BO_1_A8") (pintype "bidirectional"))
      (node (ref "X1") (pin "2") (pinfunction "1_2") (pintype "passive"))
    )
    (net (code "98") (name "Net-(U$1A-BO_2)") (class "Default")
      (node (ref "U$1") (pin "A9") (pinfunction "BO_2_A9") (pintype "bidirectional"))
      (node (ref "X1") (pin "3") (pinfunction "1_3") (pintype "passive"))
    )
    (net (code "99") (name "Net-(U$1A-BO_3)") (class "Default")
      (node (ref "U$1") (pin "A10") (pinfunction "BO_3_A10") (pintype "bidirectional"))
      (node (ref "X1") (pin "4") (pinfunction "1_4") (pintype "passive"))
    )
    (net (code "100") (name "Net-(U$2A-BO_0)") (class "Default")
      (node (ref "U$2") (pin "A7") (pinfunction "BO_0_A7") (pintype "bidirectional"))
      (node (ref "X2") (pin "4") (pinfunction "1_4") (pintype "passive"))
    )
    (net (code "101") (name "Net-(U$2A-BO_1)") (class "Default")
      (node (ref "U$2") (pin "A8") (pinfunction "BO_1_A8") (pintype "bidirectional"))
      (node (ref "X2") (pin "3") (pinfunction "1_3") (pintype "passive"))
    )
    (net (code "102") (name "Net-(U$2A-BO_2)") (class "Default")
      (node (ref "U$2") (pin "A9") (pinfunction "BO_2_A9") (pintype "bidirectional"))
      (node (ref "X2") (pin "2") (pinfunction "1_2") (pintype "passive"))
    )
    (net (code "103") (name "Net-(U$2A-BO_3)") (class "Default")
      (node (ref "U$2") (pin "A10") (pinfunction "BO_3_A10") (pintype "bidirectional"))
      (node (ref "X2") (pin "1") (pinfunction "1_1") (pintype "passive"))
    )
  )
)
